# AMU-S06-V00-CANACC.net
KiCad netlist of a schematic drawn in Altium Designer
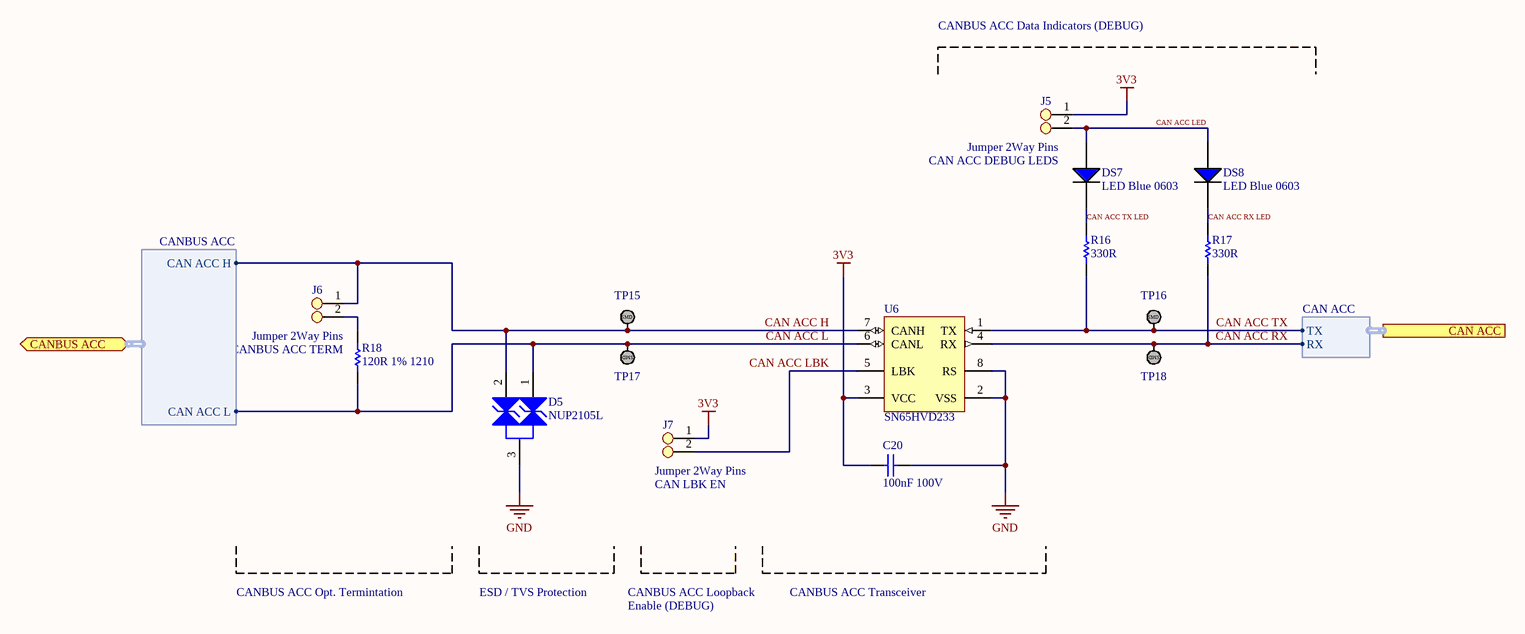
[diagram p0: AMU-S06-V00-CANACC.SchDoc]

(export (version "E")
  (design (tool "Eeschema 10.0.6"))
  (components
    (comp (ref "C20")
      (value "100nF 100V")
      (footprint "Cap_Ceramic_0603")
      (description "Capacitor, Ceramic, SMD, 100nF, 100V, 5%, X7R, 0603")
      (libsource (lib "StandardCapacitors") (part "100nF 100V 5% X7R 0603"))
    )
    (comp (ref "D5")
      (value "NUP2105L")
      (footprint "NUP2105L")
      (libsource (lib "QUTMS_CANLibrary") (part "NUP2105L"))
    )
    (comp (ref "DS7")
      (value "LED Blue 0603")
      (footprint "LED BLUE 0603")
      (libsource (lib "QUTMS_LEDLibrary") (part "LED BLUE 0603"))
    )
    (comp (ref "DS8")
      (value "LED Blue 0603")
      (footprint "LED BLUE 0603")
      (libsource (lib "QUTMS_LEDLibrary") (part "LED BLUE 0603"))
    )
    (comp (ref "J5")
      (value "Jumper 2Way Pins")
      (footprint "Jumper_2Way_Pin")
      (description "Jumper 2Way Side Pins")
      (libsource (lib "QUTMS_JumperLibrary") (part "Jumper 2Way Side Pins"))
    )
    (comp (ref "J6")
      (value "Jumper 2Way Pins")
      (footprint "Jumper_2Way_Pin")
      (description "Jumper 2Way Side Pins")
      (libsource (lib "QUTMS_JumperLibrary") (part "Jumper 2Way Side Pins"))
    )
    (comp (ref "J7")
      (value "Jumper 2Way Pins")
      (footprint "Jumper_2Way_Pin")
      (description "Jumper 2Way Side Pins")
      (libsource (lib "QUTMS_JumperLibrary") (part "Jumper 2Way Side Pins"))
    )
    (comp (ref "R16")
      (value "330R")
      (footprint "Res_ThinFilm_0603")
      (description "Resistor, SMD, 330R, 0.1W, 5%, 0603")
      (libsource (lib "StandardResistors") (part "330R 5% 0603"))
    )
    (comp (ref "R17")
      (value "330R")
      (footprint "Res_ThinFilm_0603")
      (description "Resistor, SMD, 330R, 0.1W, 5%, 0603")
      (libsource (lib "StandardResistors") (part "330R 5% 0603"))
    )
    (comp (ref "R18")
      (value "120R 1% 1210")
      (footprint "Res_ThinFilm_1210")
      (description "Resistor, SMD, 120R, 0.25W, 1%, 1210")
      (libsource (lib "StandardResistors") (part "120R 1% 1210"))
    )
    (comp (ref "TP15")
      (value "TestPoint_SMD")
      (footprint "TestPointSMD")
      (libsource (lib "StandardTest") (part "TestPoint_SMD"))
    )
    (comp (ref "TP16")
      (value "TestPoint_SMD")
      (footprint "TestPointSMD")
      (libsource (lib "StandardTest") (part "TestPoint_SMD"))
    )
    (comp (ref "TP17")
      (value "TestPoint_SMD")
      (footprint "TestPointSMD")
      (libsource (lib "StandardTest") (part "TestPoint_SMD"))
    )
    (comp (ref "TP18")
      (value "TestPoint_SMD")
      (footprint "TestPointSMD")
      (libsource (lib "StandardTest") (part "TestPoint_SMD"))
    )
    (comp (ref "U6")
      (value "SN65HVD233")
      (footprint "SN65HVD233DR")
      (libsource (lib "QUTMS_CANLibrary") (part "SN65HVD233"))
    )
  )
  (nets
    (net (code "4") (name "/CAN ACC H") (class "Default")
      (node (ref "D5") (pin "2") (pinfunction "2_2") (pintype "passive"))
      (node (ref "J6") (pin "1") (pinfunction "1_1") (pintype "passive"))
      (node (ref "TP15") (pin "1") (pinfunction "1_1") (pintype "passive"))
      (node (ref "U6") (pin "7") (pinfunction "CANH_7") (pintype "bidirectional"))
    )
    (net (code "5") (name "/CAN ACC L") (class "Default")
      (node (ref "D5") (pin "1") (pinfunction "1_1") (pintype "passive"))
      (node (ref "R18") (pin "1") (pinfunction "1_1") (pintype "passive"))
      (node (ref "TP17") (pin "1") (pinfunction "1_1") (pintype "passive"))
      (node (ref "U6") (pin "6") (pinfunction "CANL_6") (pintype "bidirectional"))
    )
    (net (code "6") (name "/CAN ACC LBK") (class "Default")
      (node (ref "J7") (pin "2") (pinfunction "2_2") (pintype "passive"))
      (node (ref "U6") (pin "5") (pinfunction "LBK_5") (pintype "passive"))
    )
    (net (code "7") (name "/CAN ACC LED") (class "Default")
      (node (ref "DS7") (pin "1") (pinfunction "A_1") (pintype "passive"))
      (node (ref "DS8") (pin "1") (pinfunction "A_1") (pintype "passive"))
      (node (ref "J5") (pin "2") (pinfunction "2_2") (pintype "passive"))
    )
    (net (code "8") (name "/CAN ACC RX") (class "Default")
      (node (ref "R17") (pin "1") (pinfunction "1_1") (pintype "passive"))
      (node (ref "TP18") (pin "1") (pinfunction "1_1") (pintype "passive"))
      (node (ref "U6") (pin "4") (pinfunction "RX_4") (pintype "output"))
    )
    (net (code "9") (name "/CAN ACC RX LED") (class "Default")
      (node (ref "DS8") (pin "2") (pinfunction "C_2") (pintype "passive"))
      (node (ref "R17") (pin "2") (pinfunction "2_2") (pintype "passive"))
    )
    (net (code "10") (name "/CAN ACC TX") (class "Default")
      (node (ref "R16") (pin "1") (pinfunction "1_1") (pintype "passive"))
      (node (ref "TP16") (pin "1") (pinfunction "1_1") (pintype "passive"))
      (node (ref "U6") (pin "1") (pinfunction "TX_1") (pintype "input"))
    )
    (net (code "11") (name "/CAN ACC TX LED") (class "Default")
      (node (ref "DS7") (pin "2") (pinfunction "C_2") (pintype "passive"))
      (node (ref "R16") (pin "2") (pinfunction "2_2") (pintype "passive"))
    )
    (net (code "14") (name "3V3") (class "Default")
      (node (ref "C20") (pin "2") (pinfunction "2_2") (pintype "passive"))
      (node (ref "J5") (pin "1") (pinfunction "1_1") (pintype "passive"))
      (node (ref "J7") (pin "1") (pinfunction "1_1") (pintype "passive"))
      (node (ref "U6") (pin "3") (pinfunction "VCC_3") (pintype "passive"))
    )
    (net (code "15") (name "GND") (class "Default")
      (node (ref "C20") (pin "1") (pinfunction "1_1") (pintype "passive"))
      (node (ref "D5") (pin "3") (pinfunction "3_3") (pintype "passive"))
      (node (ref "U6") (pin "2") (pinfunction "VSS_2") (pintype "passive"))
      (node (ref "U6") (pin "8") (pinfunction "RS_8") (pintype "passive"))
    )
    (net (code "16") (name "Net-(J6-Pad2)") (class "Default")
      (node (ref "J6") (pin "2") (pinfunction "2_2") (pintype "passive"))
      (node (ref "R18") (pin "2") (pinfunction "2_2") (pintype "passive"))
    )
  )
)
